# Team_Upsilon_Prj2_smain_sch.net
KiCad netlist of a schematic drawn in Altium Designer
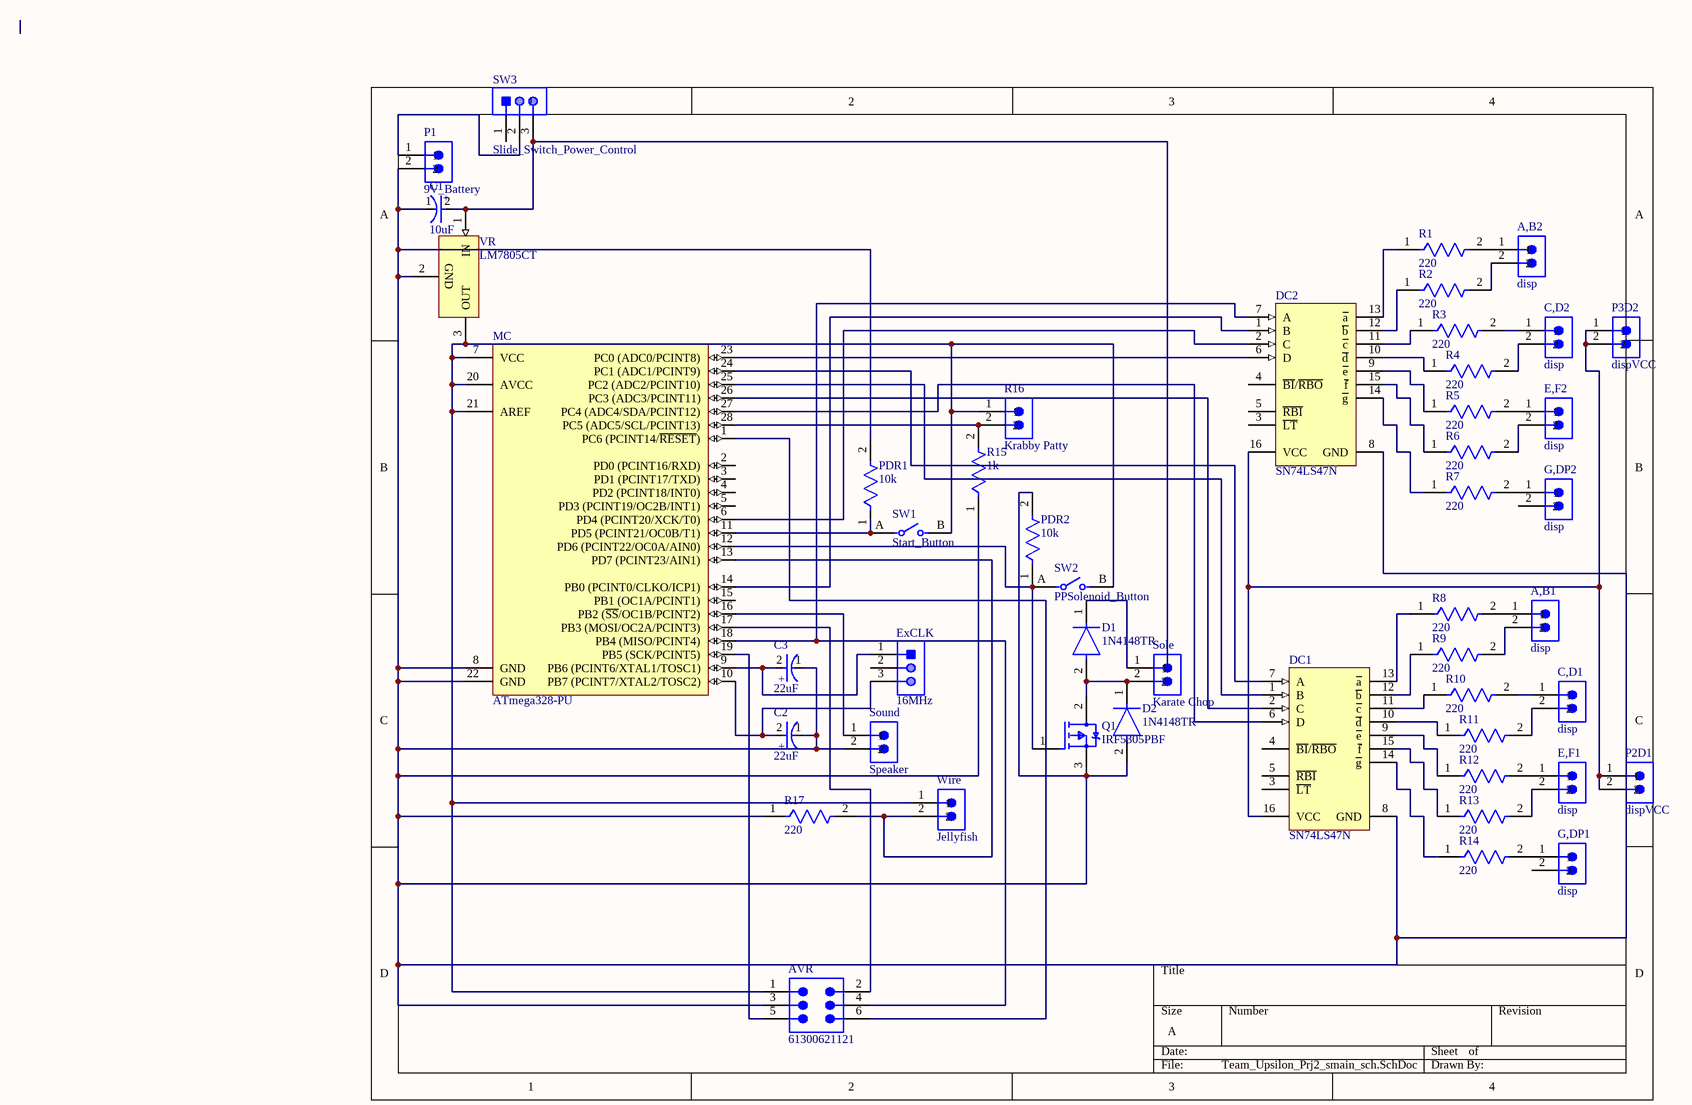
[diagram p0: Team_Upsilon_Prj2_smain_sch.SchDoc]

(export (version "E")
  (design (tool "Eeschema 10.0.6"))
  (components
    (comp (ref "A,B1")
      (value "disp")
      (footprint "61300211121")
      (libsource (lib "Altium Content Vault") (part "Header_Male_1R_02P"))
    )
    (comp (ref "A,B2")
      (value "disp")
      (footprint "61300211121")
      (libsource (lib "Altium Content Vault") (part "Header_Male_1R_02P"))
    )
    (comp (ref "AVR")
      (value "61300621121")
      (footprint "61300621121")
      (libsource (lib "Altium Content Vault") (part "Header_Male_2R_06P"))
    )
    (comp (ref "C,D1")
      (value "disp")
      (footprint "61300211121")
      (libsource (lib "Altium Content Vault") (part "Header_Male_1R_02P"))
    )
    (comp (ref "C,D2")
      (value "disp")
      (footprint "61300211121")
      (libsource (lib "Altium Content Vault") (part "Header_Male_1R_02P"))
    )
    (comp (ref "C1")
      (value "10uF")
      (footprint "FP-RAD-TH-D_10_0_5-L_20_2-MFG")
      (description "Aluminum Electrolytic Capacitors (Radial Lead Type) 10uF ±20% 400V")
      (fields (field (name "VOLTAGE") "400V") (field (name "TOLERANCE") "20%"))
      (libsource (lib "Altium Content Vault") (part "203bc49f2ac43e59fd269a8c329ed05"))
    )
    (comp (ref "C2")
      (value "22uF")
      (footprint "FP-RAD-TH-D_10_0_5-L_20_2-MFG")
      (description "Aluminum Electrolytic Capacitors (Radial Lead Type) 10uF ±20% 400V")
      (fields (field (name "VOLTAGE") "400V") (field (name "TOLERANCE") "20%"))
      (libsource (lib "Altium Content Vault") (part "203bc49f2ac43e59fd269a8c329ed05"))
    )
    (comp (ref "C3")
      (value "22uF")
      (footprint "FP-RAD-TH-D_10_0_5-L_20_2-MFG")
      (description "Aluminum Electrolytic Capacitors (Radial Lead Type) 10uF ±20% 400V")
      (fields (field (name "VOLTAGE") "400V") (field (name "TOLERANCE") "20%"))
      (libsource (lib "Altium Content Vault") (part "203bc49f2ac43e59fd269a8c329ed05"))
    )
    (comp (ref "D1")
      (value "1N4148TR")
      (footprint "FP-017AG-MFG")
      (description "DIODE GEN PURP 100V 200MA DO35")
      (fields
        (field (name "OCTOPART") "https://octopart.com/1n4148tr-on+semiconductor-84323125")
        (field (name "MANUFACTURER") "ON Semiconductor")
      )
      (libsource (lib "Altium Content Vault") (part "d7152d700b627762746794eb795d46e"))
    )
    (comp (ref "D2")
      (value "1N4148TR")
      (footprint "FP-017AG-MFG")
      (description "DIODE GEN PURP 100V 200MA DO35")
      (fields
        (field (name "OCTOPART") "https://octopart.com/1n4148tr-on+semiconductor-84323125")
        (field (name "MANUFACTURER") "ON Semiconductor")
      )
      (libsource (lib "Altium Content Vault") (part "d7152d700b627762746794eb795d46e"))
    )
    (comp (ref "DC1")
      (value "SN74LS47N")
      (footprint "N0016A")
      (description "BCD-to-7-Segment Decoder / Driver, 4.75 to 5.25 V, 0 to 70 degC, 16-pin DIP (N16), Pb-Free (RoHS)")
      (fields (field (name "MANUFACTURER") "Texas Instruments"))
      (libsource (lib "Altium Content Vault") (part "TI-SNX4XX247-16"))
    )
    (comp (ref "DC2")
      (value "SN74LS47N")
      (footprint "N0016A")
      (description "BCD-to-7-Segment Decoder / Driver, 4.75 to 5.25 V, 0 to 70 degC, 16-pin DIP (N16), Pb-Free (RoHS)")
      (fields (field (name "MANUFACTURER") "Texas Instruments"))
      (libsource (lib "Altium Content Vault") (part "TI-SNX4XX247-16"))
    )
    (comp (ref "E,F1")
      (value "disp")
      (footprint "61300211121")
      (libsource (lib "Altium Content Vault") (part "Header_Male_1R_02P"))
    )
    (comp (ref "E,F2")
      (value "disp")
      (footprint "61300211121")
      (libsource (lib "Altium Content Vault") (part "Header_Male_1R_02P"))
    )
    (comp (ref "ExCLK")
      (value "16MHz")
      (footprint "MOLX-22-28-4033_V")
      (description "Male Header, Pitch 2.54 mm, 1 x 3 Position, Height 8.38 mm, Tail Length 3.18 mm, RoHS, Bulk")
      (fields (field (name "MANUFACTURER") "Molex"))
      (libsource (lib "Altium Content Vault") (part "CN-1P-M-R3"))
    )
    (comp (ref "G,DP1")
      (value "disp")
      (footprint "61300211121")
      (libsource (lib "Altium Content Vault") (part "Header_Male_1R_02P"))
    )
    (comp (ref "G,DP2")
      (value "disp")
      (footprint "61300211121")
      (libsource (lib "Altium Content Vault") (part "Header_Male_1R_02P"))
    )
    (comp (ref "MC")
      (value "ATmega328-PU")
      (footprint "28P3")
      (libsource (lib "Altium Content Vault") (part "MC-8B-ATM48-IL28"))
    )
    (comp (ref "P1")
      (value "9V_Battery")
      (footprint "61300211121")
      (libsource (lib "Altium Content Vault") (part "Header_Male_1R_02P"))
    )
    (comp (ref "P2D1")
      (value "dispVCC")
      (footprint "61300211121")
      (libsource (lib "Altium Content Vault") (part "Header_Male_1R_02P"))
    )
    (comp (ref "P3D2")
      (value "dispVCC")
      (footprint "61300211121")
      (libsource (lib "Altium Content Vault") (part "Header_Male_1R_02P"))
    )
    (comp (ref "PDR1")
      (value "10k")
      (footprint "FP-MBB0207-MFG")
      (description "RES 10K OHM 0.6W 1% AXIAL")
      (fields (field (name "TOLERANCE") "1%"))
      (libsource (lib "Altium Content Vault") (part "1029c3af85768c4190bb7ad29bc67b5"))
    )
    (comp (ref "PDR2")
      (value "10k")
      (footprint "FP-MBB0207-MFG")
      (description "RES 10K OHM 0.6W 1% AXIAL")
      (fields (field (name "TOLERANCE") "1%"))
      (libsource (lib "Altium Content Vault") (part "1029c3af85768c4190bb7ad29bc67b5"))
    )
    (comp (ref "Q1")
      (value "IRF5305PBF")
      (footprint "FP-PG-TO220-3-0")
      (description "MOSFET P-CH 55V 31A TO-220AB")
      (fields
        (field (name "OCTOPART") "https://octopart.com/irf5305pbf-infineon-65873396")
        (field (name "MANUFACTURER") "Infineon")
      )
      (libsource (lib "Altium Content Vault") (part "ef9d0aacdf366ab529cd174aea9d313"))
    )
    (comp (ref "R1")
      (value "220")
      (footprint "FP-MBB0207-MFG")
      (description "RES 10K OHM 0.6W 1% AXIAL")
      (fields (field (name "TOLERANCE") "1%"))
      (libsource (lib "Altium Content Vault") (part "1029c3af85768c4190bb7ad29bc67b5"))
    )
    (comp (ref "R2")
      (value "220")
      (footprint "FP-MBB0207-MFG")
      (description "RES 10K OHM 0.6W 1% AXIAL")
      (fields (field (name "TOLERANCE") "1%"))
      (libsource (lib "Altium Content Vault") (part "1029c3af85768c4190bb7ad29bc67b5"))
    )
    (comp (ref "R3")
      (value "220")
      (footprint "FP-MBB0207-MFG")
      (description "RES 10K OHM 0.6W 1% AXIAL")
      (fields (field (name "TOLERANCE") "1%"))
      (libsource (lib "Altium Content Vault") (part "1029c3af85768c4190bb7ad29bc67b5"))
    )
    (comp (ref "R4")
      (value "220")
      (footprint "FP-MBB0207-MFG")
      (description "RES 10K OHM 0.6W 1% AXIAL")
      (fields (field (name "TOLERANCE") "1%"))
      (libsource (lib "Altium Content Vault") (part "1029c3af85768c4190bb7ad29bc67b5"))
    )
    (comp (ref "R5")
      (value "220")
      (footprint "FP-MBB0207-MFG")
      (description "RES 10K OHM 0.6W 1% AXIAL")
      (fields (field (name "TOLERANCE") "1%"))
      (libsource (lib "Altium Content Vault") (part "1029c3af85768c4190bb7ad29bc67b5"))
    )
    (comp (ref "R6")
      (value "220")
      (footprint "FP-MBB0207-MFG")
      (description "RES 10K OHM 0.6W 1% AXIAL")
      (fields (field (name "TOLERANCE") "1%"))
      (libsource (lib "Altium Content Vault") (part "1029c3af85768c4190bb7ad29bc67b5"))
    )
    (comp (ref "R7")
      (value "220")
      (footprint "FP-MBB0207-MFG")
      (description "RES 10K OHM 0.6W 1% AXIAL")
      (fields (field (name "TOLERANCE") "1%"))
      (libsource (lib "Altium Content Vault") (part "1029c3af85768c4190bb7ad29bc67b5"))
    )
    (comp (ref "R8")
      (value "220")
      (footprint "FP-MBB0207-MFG")
      (description "RES 10K OHM 0.6W 1% AXIAL")
      (fields (field (name "TOLERANCE") "1%"))
      (libsource (lib "Altium Content Vault") (part "1029c3af85768c4190bb7ad29bc67b5"))
    )
    (comp (ref "R9")
      (value "220")
      (footprint "FP-MBB0207-MFG")
      (description "RES 10K OHM 0.6W 1% AXIAL")
      (fields (field (name "TOLERANCE") "1%"))
      (libsource (lib "Altium Content Vault") (part "1029c3af85768c4190bb7ad29bc67b5"))
    )
    (comp (ref "R10")
      (value "220")
      (footprint "FP-MBB0207-MFG")
      (description "RES 10K OHM 0.6W 1% AXIAL")
      (fields (field (name "TOLERANCE") "1%"))
      (libsource (lib "Altium Content Vault") (part "1029c3af85768c4190bb7ad29bc67b5"))
    )
    (comp (ref "R11")
      (value "220")
      (footprint "FP-MBB0207-MFG")
      (description "RES 10K OHM 0.6W 1% AXIAL")
      (fields (field (name "TOLERANCE") "1%"))
      (libsource (lib "Altium Content Vault") (part "1029c3af85768c4190bb7ad29bc67b5"))
    )
    (comp (ref "R12")
      (value "220")
      (footprint "FP-MBB0207-MFG")
      (description "RES 10K OHM 0.6W 1% AXIAL")
      (fields (field (name "TOLERANCE") "1%"))
      (libsource (lib "Altium Content Vault") (part "1029c3af85768c4190bb7ad29bc67b5"))
    )
    (comp (ref "R13")
      (value "220")
      (footprint "FP-MBB0207-MFG")
      (description "RES 10K OHM 0.6W 1% AXIAL")
      (fields (field (name "TOLERANCE") "1%"))
      (libsource (lib "Altium Content Vault") (part "1029c3af85768c4190bb7ad29bc67b5"))
    )
    (comp (ref "R14")
      (value "220")
      (footprint "FP-MBB0207-MFG")
      (description "RES 10K OHM 0.6W 1% AXIAL")
      (fields (field (name "TOLERANCE") "1%"))
      (libsource (lib "Altium Content Vault") (part "1029c3af85768c4190bb7ad29bc67b5"))
    )
    (comp (ref "R15")
      (value "1k")
      (footprint "FP-MBB0207-MFG")
      (description "RES 10K OHM 0.6W 1% AXIAL")
      (fields (field (name "TOLERANCE") "1%"))
      (libsource (lib "Altium Content Vault") (part "1029c3af85768c4190bb7ad29bc67b5"))
    )
    (comp (ref "R16")
      (value "Krabby Patty")
      (footprint "61300211121")
      (libsource (lib "Altium Content Vault") (part "Header_Male_1R_02P"))
    )
    (comp (ref "R17")
      (value "220")
      (footprint "FP-MBB0207-MFG")
      (description "RES 10K OHM 0.6W 1% AXIAL")
      (fields (field (name "TOLERANCE") "1%"))
      (libsource (lib "Altium Content Vault") (part "1029c3af85768c4190bb7ad29bc67b5"))
    )
    (comp (ref "Sole")
      (value "Karate Chop")
      (footprint "61300211121")
      (libsource (lib "Altium Content Vault") (part "Header_Male_1R_02P"))
    )
    (comp (ref "Sound")
      (value "Speaker")
      (footprint "61300211121")
      (libsource (lib "Altium Content Vault") (part "Header_Male_1R_02P"))
    )
    (comp (ref "SW1")
      (value "Start_Button")
      (footprint "FP-EVQ11Y04K-MFG")
      (description "SWITCH TACTILE SPST-NO 0.02A 15V")
      (libsource (lib "Altium Content Vault") (part "2b0b2b19372efd94fa7681498149756"))
    )
    (comp (ref "SW2")
      (value "PPSolenoid_Button")
      (footprint "FP-EVQ11Y04K-MFG")
      (description "SWITCH TACTILE SPST-NO 0.02A 15V")
      (libsource (lib "Altium Content Vault") (part "2b0b2b19372efd94fa7681498149756"))
    )
    (comp (ref "SW3")
      (value "Slide_Switch_Power_Control")
      (footprint "MOLX-22-28-4033_V")
      (description "Male Header, Pitch 2.54 mm, 1 x 3 Position, Height 8.38 mm, Tail Length 3.18 mm, RoHS, Bulk")
      (fields (field (name "MANUFACTURER") "Molex"))
      (libsource (lib "") (part "CN-1P-M-R3_1"))
    )
    (comp (ref "VR")
      (value "LM7805CT")
      (footprint "FAIR-TO-220-3")
      (description "Positive Voltage Regulator, 5 V, 1 A, -40 to 125 degC, 3-Pin TO-220, RoHS, Tube")
      (fields (field (name "MANUFACTURER") "FairchildSemiconductor"))
      (libsource (lib "Altium Content Vault") (part "FAIR-LM7805CT-TO220-3"))
    )
    (comp (ref "Wire")
      (value "Jellyfish")
      (footprint "61300211121")
      (libsource (lib "Altium Content Vault") (part "Header_Male_1R_02P"))
    )
  )
  (nets
    (net (code "1") (name "Net-(A,B1-Pad1)") (class "Default")
      (node (ref "A,B1") (pin "1") (pinfunction "1_1") (pintype "passive"))
      (node (ref "R8") (pin "2") (pinfunction "2_2") (pintype "passive"))
    )
    (net (code "2") (name "Net-(A,B1-Pad2)") (class "Default")
      (node (ref "A,B1") (pin "2") (pinfunction "2_2") (pintype "passive"))
      (node (ref "R9") (pin "2") (pinfunction "2_2") (pintype "passive"))
    )
    (net (code "3") (name "Net-(A,B2-Pad1)") (class "Default")
      (node (ref "A,B2") (pin "1") (pinfunction "1_1") (pintype "passive"))
      (node (ref "R1") (pin "2") (pinfunction "2_2") (pintype "passive"))
    )
    (net (code "4") (name "Net-(A,B2-Pad2)") (class "Default")
      (node (ref "A,B2") (pin "2") (pinfunction "2_2") (pintype "passive"))
      (node (ref "R2") (pin "2") (pinfunction "2_2") (pintype "passive"))
    )
    (net (code "5") (name "Net-(C,D1-Pad1)") (class "Default")
      (node (ref "C,D1") (pin "1") (pinfunction "1_1") (pintype "passive"))
      (node (ref "R10") (pin "2") (pinfunction "2_2") (pintype "passive"))
    )
    (net (code "6") (name "Net-(C,D1-Pad2)") (class "Default")
      (node (ref "C,D1") (pin "2") (pinfunction "2_2") (pintype "passive"))
      (node (ref "R11") (pin "2") (pinfunction "2_2") (pintype "passive"))
    )
    (net (code "7") (name "Net-(C,D2-Pad1)") (class "Default")
      (node (ref "C,D2") (pin "1") (pinfunction "1_1") (pintype "passive"))
      (node (ref "R3") (pin "2") (pinfunction "2_2") (pintype "passive"))
    )
    (net (code "8") (name "Net-(C,D2-Pad2)") (class "Default")
      (node (ref "C,D2") (pin "2") (pinfunction "2_2") (pintype "passive"))
      (node (ref "R4") (pin "2") (pinfunction "2_2") (pintype "passive"))
    )
    (net (code "9") (name "Net-(C1-A)") (class "Default")
      (node (ref "C1") (pin "2") (pinfunction "A_2") (pintype "passive"))
      (node (ref "SW3") (pin "3") (pinfunction "3_3") (pintype "passive"))
      (node (ref "VR") (pin "1") (pinfunction "IN_1") (pintype "input"))
    )
    (net (code "10") (name "Net-(C1-C)") (class "Default")
      (node (ref "AVR") (pin "3") (pinfunction "3_3") (pintype "passive"))
      (node (ref "C1") (pin "1") (pinfunction "C_1") (pintype "passive"))
      (node (ref "C2") (pin "1") (pinfunction "C_1") (pintype "passive"))
      (node (ref "C3") (pin "1") (pinfunction "C_1") (pintype "passive"))
      (node (ref "D2") (pin "2") (pinfunction "A_2") (pintype "passive"))
      (node (ref "DC1") (pin "8") (pinfunction "GND_8") (pintype "power_in"))
      (node (ref "DC2") (pin "8") (pinfunction "GND_8") (pintype "power_in"))
      (node (ref "MC") (pin "22") (pinfunction "GND_22") (pintype "power_in"))
      (node (ref "MC") (pin "8") (pinfunction "GND_8") (pintype "power_in"))
      (node (ref "P1") (pin "2") (pinfunction "2_2") (pintype "passive"))
      (node (ref "PDR1") (pin "2") (pinfunction "2_2") (pintype "passive"))
      (node (ref "PDR2") (pin "2") (pinfunction "2_2") (pintype "passive"))
      (node (ref "Q1") (pin "3") (pinfunction "S_3") (pintype "passive"))
      (node (ref "R15") (pin "1") (pinfunction "1_1") (pintype "passive"))
      (node (ref "R17") (pin "1") (pinfunction "1_1") (pintype "passive"))
      (node (ref "Sound") (pin "2") (pinfunction "2_2") (pintype "passive"))
      (node (ref "VR") (pin "2") (pinfunction "GND_2") (pintype "power_in"))
    )
    (net (code "11") (name "Net-(C2-A)") (class "Default")
      (node (ref "C2") (pin "2") (pinfunction "A_2") (pintype "passive"))
      (node (ref "ExCLK") (pin "3") (pinfunction "3_3") (pintype "passive"))
      (node (ref "MC") (pin "10") (pinfunction "PB7_(PCINT7/XTAL2/TOSC2)_10") (pintype "bidirectional"))
    )
    (net (code "12") (name "Net-(C3-A)") (class "Default")
      (node (ref "C3") (pin "2") (pinfunction "A_2") (pintype "passive"))
      (node (ref "ExCLK") (pin "1") (pinfunction "1_1") (pintype "passive"))
      (node (ref "MC") (pin "9") (pinfunction "PB6_(PCINT6/XTAL1/TOSC1)_9") (pintype "bidirectional"))
    )
    (net (code "13") (name "Net-(D1-A)") (class "Default")
      (node (ref "D1") (pin "2") (pinfunction "A_2") (pintype "passive"))
      (node (ref "D2") (pin "1") (pinfunction "C_1") (pintype "passive"))
      (node (ref "Q1") (pin "2") (pinfunction "D_2") (pintype "passive"))
      (node (ref "Sole") (pin "2") (pinfunction "2_2") (pintype "passive"))
    )
    (net (code "14") (name "Net-(D1-C)") (class "Default")
      (node (ref "D1") (pin "1") (pinfunction "C_1") (pintype "passive"))
      (node (ref "Sole") (pin "1") (pinfunction "1_1") (pintype "passive"))
    )
    (net (code "15") (name "Net-(DC1-A)") (class "Default")
      (node (ref "DC1") (pin "7") (pinfunction "A_7") (pintype "input"))
      (node (ref "MC") (pin "24") (pinfunction "PC1_(ADC1/PCINT9)_24") (pintype "bidirectional"))
    )
    (net (code "16") (name "Net-(DC1-B)") (class "Default")
      (node (ref "DC1") (pin "1") (pinfunction "B_1") (pintype "input"))
      (node (ref "MC") (pin "25") (pinfunction "PC2_(ADC2/PCINT10)_25") (pintype "bidirectional"))
    )
    (net (code "17") (name "Net-(DC1-C)") (class "Default")
      (node (ref "DC1") (pin "2") (pinfunction "C_2") (pintype "input"))
      (node (ref "MC") (pin "26") (pinfunction "PC3_(ADC3/PCINT11)_26") (pintype "bidirectional"))
    )
    (net (code "18") (name "Net-(DC1-D)") (class "Default")
      (node (ref "DC1") (pin "6") (pinfunction "D_6") (pintype "input"))
      (node (ref "MC") (pin "27") (pinfunction "PC4_(ADC4/SDA/PCINT12)_27") (pintype "bidirectional"))
    )
    (net (code "19") (name "Net-(DC1-VCC)") (class "Default")
      (node (ref "DC1") (pin "16") (pinfunction "VCC_16") (pintype "power_in"))
      (node (ref "DC2") (pin "16") (pinfunction "VCC_16") (pintype "power_in"))
      (node (ref "P2D1") (pin "1") (pinfunction "1_1") (pintype "passive"))
      (node (ref "P2D1") (pin "2") (pinfunction "2_2") (pintype "passive"))
      (node (ref "P3D2") (pin "1") (pinfunction "1_1") (pintype "passive"))
      (node (ref "P3D2") (pin "2") (pinfunction "2_2") (pintype "passive"))
    )
    (net (code "20") (name "Net-(DC1-~{a})") (class "Default")
      (node (ref "DC1") (pin "13") (pinfunction "~{a}_13") (pintype "open_collector"))
      (node (ref "R8") (pin "1") (pinfunction "1_1") (pintype "passive"))
    )
    (net (code "21") (name "Net-(DC1-~{b})") (class "Default")
      (node (ref "DC1") (pin "12") (pinfunction "~{b}_12") (pintype "open_collector"))
      (node (ref "R9") (pin "1") (pinfunction "1_1") (pintype "passive"))
    )
    (net (code "22") (name "Net-(DC1-~{c})") (class "Default")
      (node (ref "DC1") (pin "11") (pinfunction "~{c}_11") (pintype "open_collector"))
      (node (ref "R10") (pin "1") (pinfunction "1_1") (pintype "passive"))
    )
    (net (code "23") (name "Net-(DC1-~{d})") (class "Default")
      (node (ref "DC1") (pin "10") (pinfunction "~{d}_10") (pintype "open_collector"))
      (node (ref "R11") (pin "1") (pinfunction "1_1") (pintype "passive"))
    )
    (net (code "24") (name "Net-(DC1-~{e})") (class "Default")
      (node (ref "DC1") (pin "9") (pinfunction "~{e}_9") (pintype "open_collector"))
      (node (ref "R12") (pin "1") (pinfunction "1_1") (pintype "passive"))
    )
    (net (code "25") (name "Net-(DC1-~{f})") (class "Default")
      (node (ref "DC1") (pin "15") (pinfunction "~{f}_15") (pintype "open_collector"))
      (node (ref "R13") (pin "1") (pinfunction "1_1") (pintype "passive"))
    )
    (net (code "26") (name "Net-(DC1-~{g})") (class "Default")
      (node (ref "DC1") (pin "14") (pinfunction "~{g}_14") (pintype "open_collector"))
      (node (ref "R14") (pin "1") (pinfunction "1_1") (pintype "passive"))
    )
    (net (code "27") (name "Net-(DC2-A)") (class "Default")
      (node (ref "AVR") (pin "4") (pinfunction "4_4") (pintype "passive"))
      (node (ref "DC2") (pin "7") (pinfunction "A_7") (pintype "input"))
      (node (ref "MC") (pin "18") (pinfunction "PB4_(MISO/PCINT4)_18") (pintype "bidirectional"))
    )
    (net (code "28") (name "Net-(DC2-B)") (class "Default")
      (node (ref "DC2") (pin "1") (pinfunction "B_1") (pintype "input"))
      (node (ref "MC") (pin "14") (pinfunction "PB0_(PCINT0/CLKO/ICP1)_14") (pintype "bidirectional"))
    )
    (net (code "29") (name "Net-(DC2-C)") (class "Default")
      (node (ref "DC2") (pin "2") (pinfunction "C_2") (pintype "input"))
      (node (ref "MC") (pin "6") (pinfunction "PD4_(PCINT20/XCK/T0)_6") (pintype "bidirectional"))
    )
    (net (code "30") (name "Net-(DC2-D)") (class "Default")
      (node (ref "DC2") (pin "6") (pinfunction "D_6") (pintype "input"))
      (node (ref "MC") (pin "23") (pinfunction "PC0_(ADC0/PCINT8)_23") (pintype "bidirectional"))
    )
    (net (code "31") (name "Net-(DC2-~{a})") (class "Default")
      (node (ref "DC2") (pin "13") (pinfunction "~{a}_13") (pintype "open_collector"))
      (node (ref "R1") (pin "1") (pinfunction "1_1") (pintype "passive"))
    )
    (net (code "32") (name "Net-(DC2-~{b})") (class "Default")
      (node (ref "DC2") (pin "12") (pinfunction "~{b}_12") (pintype "open_collector"))
      (node (ref "R2") (pin "1") (pinfunction "1_1") (pintype "passive"))
    )
    (net (code "33") (name "Net-(DC2-~{c})") (class "Default")
      (node (ref "DC2") (pin "11") (pinfunction "~{c}_11") (pintype "open_collector"))
      (node (ref "R3") (pin "1") (pinfunction "1_1") (pintype "passive"))
    )
    (net (code "34") (name "Net-(DC2-~{d})") (class "Default")
      (node (ref "DC2") (pin "10") (pinfunction "~{d}_10") (pintype "open_collector"))
      (node (ref "R4") (pin "1") (pinfunction "1_1") (pintype "passive"))
    )
    (net (code "35") (name "Net-(DC2-~{e})") (class "Default")
      (node (ref "DC2") (pin "9") (pinfunction "~{e}_9") (pintype "open_collector"))
      (node (ref "R5") (pin "1") (pinfunction "1_1") (pintype "passive"))
    )
    (net (code "36") (name "Net-(DC2-~{f})") (class "Default")
      (node (ref "DC2") (pin "15") (pinfunction "~{f}_15") (pintype "open_collector"))
      (node (ref "R6") (pin "1") (pinfunction "1_1") (pintype "passive"))
    )
    (net (code "37") (name "Net-(DC2-~{g})") (class "Default")
      (node (ref "DC2") (pin "14") (pinfunction "~{g}_14") (pintype "open_collector"))
      (node (ref "R7") (pin "1") (pinfunction "1_1") (pintype "passive"))
    )
    (net (code "38") (name "Net-(E,F1-Pad1)") (class "Default")
      (node (ref "E,F1") (pin "1") (pinfunction "1_1") (pintype "passive"))
      (node (ref "R12") (pin "2") (pinfunction "2_2") (pintype "passive"))
    )
    (net (code "39") (name "Net-(E,F1-Pad2)") (class "Default")
      (node (ref "E,F1") (pin "2") (pinfunction "2_2") (pintype "passive"))
      (node (ref "R13") (pin "2") (pinfunction "2_2") (pintype "passive"))
    )
    (net (code "40") (name "Net-(E,F2-Pad1)") (class "Default")
      (node (ref "E,F2") (pin "1") (pinfunction "1_1") (pintype "passive"))
      (node (ref "R5") (pin "2") (pinfunction "2_2") (pintype "passive"))
    )
    (net (code "41") (name "Net-(E,F2-Pad2)") (class "Default")
      (node (ref "E,F2") (pin "2") (pinfunction "2_2") (pintype "passive"))
      (node (ref "R6") (pin "2") (pinfunction "2_2") (pintype "passive"))
    )
    (net (code "42") (name "Net-(G,DP1-Pad1)") (class "Default")
      (node (ref "G,DP1") (pin "1") (pinfunction "1_1") (pintype "passive"))
      (node (ref "R14") (pin "2") (pinfunction "2_2") (pintype "passive"))
    )
    (net (code "43") (name "Net-(G,DP2-Pad1)") (class "Default")
      (node (ref "G,DP2") (pin "1") (pinfunction "1_1") (pintype "passive"))
      (node (ref "R7") (pin "2") (pinfunction "2_2") (pintype "passive"))
    )
    (net (code "44") (name "Net-(MC-AREF)") (class "Default")
      (node (ref "AVR") (pin "1") (pinfunction "1_1") (pintype "passive"))
      (node (ref "MC") (pin "20") (pinfunction "AVCC_20") (pintype "power_in"))
      (node (ref "MC") (pin "21") (pinfunction "AREF_21") (pintype "power_in"))
      (node (ref "MC") (pin "7") (pinfunction "VCC_7") (pintype "power_in"))
      (node (ref "R16") (pin "1") (pinfunction "1_1") (pintype "passive"))
      (node (ref "SW1") (pin "B") (pinfunction "B_B") (pintype "passive"))
      (node (ref "SW2") (pin "B") (pinfunction "B_B") (pintype "passive"))
      (node (ref "VR") (pin "3") (pinfunction "OUT_3") (pintype "power_in"))
      (node (ref "Wire") (pin "1") (pinfunction "1_1") (pintype "passive"))
    )
    (net (code "45") (name "Net-(MC-PB2_(~{SS}{slash}OC1B{slash}PCINT2))") (class "Default")
      (node (ref "MC") (pin "16") (pinfunction "PB2_(~{SS}/OC1B/PCINT2)_16") (pintype "bidirectional"))
      (node (ref "Sound") (pin "1") (pinfunction "1_1") (pintype "passive"))
    )
    (net (code "46") (name "Net-(MC-PB3_(MOSI{slash}OC2A{slash}PCINT3))") (class "Default")
      (node (ref "AVR") (pin "2") (pinfunction "2_2") (pintype "passive"))
      (node (ref "MC") (pin "17") (pinfunction "PB3_(MOSI/OC2A/PCINT3)_17") (pintype "bidirectional"))
    )
    (net (code "47") (name "Net-(MC-PB5_(SCK{slash}PCINT5))") (class "Default")
      (node (ref "AVR") (pin "5") (pinfunction "5_5") (pintype "passive"))
      (node (ref "MC") (pin "19") (pinfunction "PB5_(SCK/PCINT5)_19") (pintype "bidirectional"))
    )
    (net (code "48") (name "Net-(MC-PC5_(ADC5{slash}SCL{slash}PCINT13))") (class "Default")
      (node (ref "MC") (pin "28") (pinfunction "PC5_(ADC5/SCL/PCINT13)_28") (pintype "bidirectional"))
      (node (ref "R15") (pin "2") (pinfunction "2_2") (pintype "passive"))
      (node (ref "R16") (pin "2") (pinfunction "2_2") (pintype "passive"))
    )
    (net (code "49") (name "Net-(MC-PC6_(PCINT14{slash}~{RESET}))") (class "Default")
      (node (ref "AVR") (pin "6") (pinfunction "6_6") (pintype "passive"))
      (node (ref "MC") (pin "1") (pinfunction "PC6_(PCINT14/~{RESET})_1") (pintype "bidirectional"))
    )
    (net (code "50") (name "Net-(MC-PD5_(PCINT21{slash}OC0B{slash}T1))") (class "Default")
      (node (ref "MC") (pin "11") (pinfunction "PD5_(PCINT21/OC0B/T1)_11") (pintype "bidirectional"))
      (node (ref "PDR1") (pin "1") (pinfunction "1_1") (pintype "passive"))
      (node (ref "SW1") (pin "A") (pinfunction "A_A") (pintype "passive"))
    )
    (net (code "51") (name "Net-(MC-PD6_(PCINT22{slash}OC0A{slash}AIN0))") (class "Default")
      (node (ref "MC") (pin "12") (pinfunction "PD6_(PCINT22/OC0A/AIN0)_12") (pintype "bidirectional"))
      (node (ref "PDR2") (pin "1") (pinfunction "1_1") (pintype "passive"))
      (node (ref "Q1") (pin "1") (pinfunction "G_1") (pintype "passive"))
      (node (ref "SW2") (pin "A") (pinfunction "A_A") (pintype "passive"))
    )
    (net (code "52") (name "Net-(MC-PD7_(PCINT23{slash}AIN1))") (class "Default")
      (node (ref "MC") (pin "13") (pinfunction "PD7_(PCINT23/AIN1)_13") (pintype "bidirectional"))
      (node (ref "R17") (pin "2") (pinfunction "2_2") (pintype "passive"))
      (node (ref "Wire") (pin "2") (pinfunction "2_2") (pintype "passive"))
    )
    (net (code "53") (name "Net-(P1-Pad1)") (class "Default")
      (node (ref "P1") (pin "1") (pinfunction "1_1") (pintype "passive"))
      (node (ref "SW3") (pin "2") (pinfunction "2_2") (pintype "passive"))
    )
    (net (code "54") (name "unconnected-(DC1-~{BI}{slash}~{RBO}-Pad4)") (class "Default")
      (node (ref "DC1") (pin "4") (pinfunction "~{BI}/~{RBO}_4") (pintype "passive"))
    )
    (net (code "55") (name "unconnected-(DC1-~{LT}-Pad3)") (class "Default")
      (node (ref "DC1") (pin "3") (pinfunction "~{LT}_3") (pintype "passive"))
    )
    (net (code "56") (name "unconnected-(DC1-~{RBI}-Pad5)") (class "Default")
      (node (ref "DC1") (pin "5") (pinfunction "~{RBI}_5") (pintype "passive"))
    )
    (net (code "57") (name "unconnected-(DC2-~{BI}{slash}~{RBO}-Pad4)") (class "Default")
      (node (ref "DC2") (pin "4") (pinfunction "~{BI}/~{RBO}_4") (pintype "passive"))
    )
    (net (code "58") (name "unconnected-(DC2-~{LT}-Pad3)") (class "Default")
      (node (ref "DC2") (pin "3") (pinfunction "~{LT}_3") (pintype "passive"))
    )
    (net (code "59") (name "unconnected-(DC2-~{RBI}-Pad5)") (class "Default")
      (node (ref "DC2") (pin "5") (pinfunction "~{RBI}_5") (pintype "passive"))
    )
    (net (code "60") (name "unconnected-(ExCLK-Pad2)") (class "Default")
      (node (ref "ExCLK") (pin "2") (pinfunction "2_2") (pintype "passive"))
    )
    (net (code "61") (name "unconnected-(G,DP1-Pad2)") (class "Default")
      (node (ref "G,DP1") (pin "2") (pinfunction "2_2") (pintype "passive"))
    )
    (net (code "62") (name "unconnected-(G,DP2-Pad2)") (class "Default")
      (node (ref "G,DP2") (pin "2") (pinfunction "2_2") (pintype "passive"))
    )
    (net (code "63") (name "unconnected-(MC-PB1_(OC1A{slash}PCINT1)-Pad15)") (class "Default")
      (node (ref "MC") (pin "15") (pinfunction "PB1_(OC1A/PCINT1)_15") (pintype "bidirectional"))
    )
    (net (code "64") (name "unconnected-(MC-PD0_(PCINT16{slash}RXD)-Pad2)") (class "Default")
      (node (ref "MC") (pin "2") (pinfunction "PD0_(PCINT16/RXD)_2") (pintype "bidirectional"))
    )
    (net (code "65") (name "unconnected-(MC-PD1_(PCINT17{slash}TXD)-Pad3)") (class "Default")
      (node (ref "MC") (pin "3") (pinfunction "PD1_(PCINT17/TXD)_3") (pintype "bidirectional"))
    )
    (net (code "66") (name "unconnected-(MC-PD2_(PCINT18{slash}INT0)-Pad4)") (class "Default")
      (node (ref "MC") (pin "4") (pinfunction "PD2_(PCINT18/INT0)_4") (pintype "bidirectional"))
    )
    (net (code "67") (name "unconnected-(MC-PD3_(PCINT19{slash}OC2B{slash}INT1)-Pad5)") (class "Default")
      (node (ref "MC") (pin "5") (pinfunction "PD3_(PCINT19/OC2B/INT1)_5") (pintype "bidirectional"))
    )
    (net (code "68") (name "unconnected-(SW3-Pad1)") (class "Default")
      (node (ref "SW3") (pin "1") (pinfunction "1_1") (pintype "passive"))
    )
  )
)
